# signal-generator.net
KiCad netlist of a schematic drawn in EAGLE
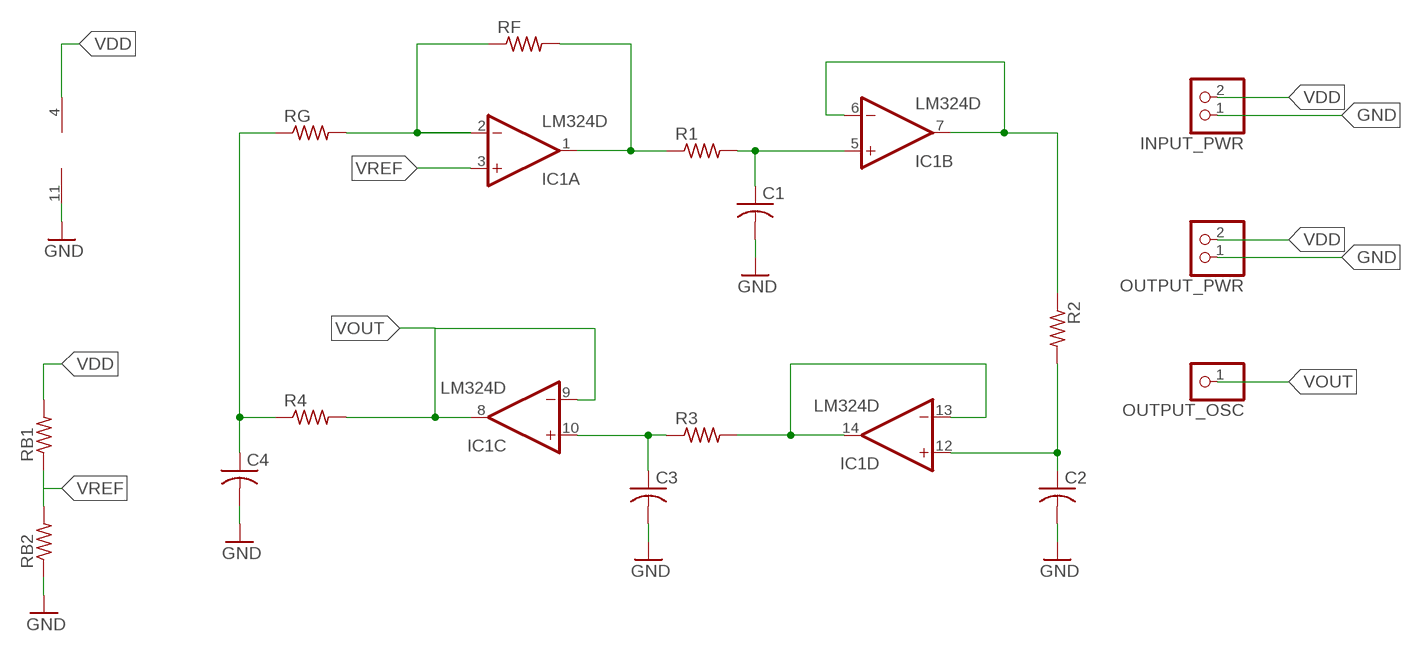
[diagram p0: schematic, sheet 1]

(export (version "E")
  (design (tool "Eeschema 10.0.6"))
  (components
    (comp (ref "C1")
      (value "C-USC0805")
      (footprint "eagle-import:C0805")
      (libsource (lib "eagle-import") (part "C-USC0805"))
    )
    (comp (ref "C2")
      (value "C-USC0805")
      (footprint "eagle-import:C0805")
      (libsource (lib "eagle-import") (part "C-USC0805"))
    )
    (comp (ref "C3")
      (value "C-USC0805")
      (footprint "eagle-import:C0805")
      (libsource (lib "eagle-import") (part "C-USC0805"))
    )
    (comp (ref "C4")
      (value "C-USC0805")
      (footprint "eagle-import:C0805")
      (libsource (lib "eagle-import") (part "C-USC0805"))
    )
    (comp (ref "IC1")
      (value "LM324D")
      (footprint "eagle-import:SO14")
      (libsource (lib "eagle-import") (part "LM324D"))
    )
    (comp (ref "INPUT_PWR")
      (value "PINHD-1X2/90")
      (footprint "eagle-import:1X02_90")
      (libsource (lib "eagle-import") (part "PINHD-1X2/90"))
    )
    (comp (ref "OUTPUT_OSC")
      (value "PINHD-1X1")
      (footprint "eagle-import:1X01")
      (libsource (lib "eagle-import") (part "PINHD-1X1"))
    )
    (comp (ref "OUTPUT_PWR")
      (value "PINHD-1X2/90")
      (footprint "eagle-import:1X02_90")
      (libsource (lib "eagle-import") (part "PINHD-1X2/90"))
    )
    (comp (ref "R1")
      (value "R-US_R0805")
      (footprint "eagle-import:R0805")
      (libsource (lib "eagle-import") (part "R-US_R0805"))
    )
    (comp (ref "R2")
      (value "R-US_R0805")
      (footprint "eagle-import:R0805")
      (libsource (lib "eagle-import") (part "R-US_R0805"))
    )
    (comp (ref "R3")
      (value "R-US_R0805")
      (footprint "eagle-import:R0805")
      (libsource (lib "eagle-import") (part "R-US_R0805"))
    )
    (comp (ref "R4")
      (value "R-US_R0805")
      (footprint "eagle-import:R0805")
      (libsource (lib "eagle-import") (part "R-US_R0805"))
    )
    (comp (ref "RB1")
      (value "R-US_R0805")
      (footprint "eagle-import:R0805")
      (libsource (lib "eagle-import") (part "R-US_R0805"))
    )
    (comp (ref "RB2")
      (value "R-US_R0805")
      (footprint "eagle-import:R0805")
      (libsource (lib "eagle-import") (part "R-US_R0805"))
    )
    (comp (ref "RF")
      (value "R-US_R0805")
      (footprint "eagle-import:R0805")
      (libsource (lib "eagle-import") (part "R-US_R0805"))
    )
    (comp (ref "RG")
      (value "R-US_R0805")
      (footprint "eagle-import:R0805")
      (libsource (lib "eagle-import") (part "R-US_R0805"))
    )
  )
  (nets
    (net (code "1") (name "GND") (class "Default")
      (node (ref "C1") (pin "2") (pinfunction "2_2") (pintype "passive"))
      (node (ref "C2") (pin "2") (pinfunction "2_2") (pintype "passive"))
      (node (ref "C3") (pin "2") (pinfunction "2_2") (pintype "passive"))
      (node (ref "C4") (pin "2") (pinfunction "2_2") (pintype "passive"))
      (node (ref "IC1") (pin "11") (pinfunction "V-_11") (pintype "power_in"))
      (node (ref "INPUT_PWR") (pin "1") (pinfunction "1_1") (pintype "passive"))
      (node (ref "OUTPUT_PWR") (pin "1") (pinfunction "1_1") (pintype "passive"))
      (node (ref "RB2") (pin "1") (pinfunction "1_1") (pintype "passive"))
    )
    (net (code "2") (name "Net-(C4-Pad1)") (class "Default")
      (node (ref "C4") (pin "1") (pinfunction "1_1") (pintype "passive"))
      (node (ref "R4") (pin "1") (pinfunction "1_1") (pintype "passive"))
      (node (ref "RG") (pin "1") (pinfunction "1_1") (pintype "passive"))
    )
    (net (code "3") (name "Net-(IC1A--IN)") (class "Default")
      (node (ref "IC1") (pin "2") (pinfunction "-IN_2") (pintype "input"))
      (node (ref "RF") (pin "1") (pinfunction "1_1") (pintype "passive"))
      (node (ref "RG") (pin "2") (pinfunction "2_2") (pintype "passive"))
    )
    (net (code "4") (name "Net-(IC1A-OUT)") (class "Default")
      (node (ref "IC1") (pin "1") (pinfunction "OUT_1") (pintype "output"))
      (node (ref "R1") (pin "1") (pinfunction "1_1") (pintype "passive"))
      (node (ref "RF") (pin "2") (pinfunction "2_2") (pintype "passive"))
    )
    (net (code "5") (name "Net-(IC1B-+IN)") (class "Default")
      (node (ref "C1") (pin "1") (pinfunction "1_1") (pintype "passive"))
      (node (ref "IC1") (pin "5") (pinfunction "+IN_5") (pintype "input"))
      (node (ref "R1") (pin "2") (pinfunction "2_2") (pintype "passive"))
    )
    (net (code "6") (name "Net-(IC1B--IN)") (class "Default")
      (node (ref "IC1") (pin "6") (pinfunction "-IN_6") (pintype "input"))
      (node (ref "IC1") (pin "7") (pinfunction "OUT_7") (pintype "output"))
      (node (ref "R2") (pin "1") (pinfunction "1_1") (pintype "passive"))
    )
    (net (code "7") (name "Net-(IC1C-+IN)") (class "Default")
      (node (ref "C3") (pin "1") (pinfunction "1_1") (pintype "passive"))
      (node (ref "IC1") (pin "10") (pinfunction "+IN_10") (pintype "input"))
      (node (ref "R3") (pin "1") (pinfunction "1_1") (pintype "passive"))
    )
    (net (code "8") (name "Net-(IC1D-+IN)") (class "Default")
      (node (ref "C2") (pin "1") (pinfunction "1_1") (pintype "passive"))
      (node (ref "IC1") (pin "12") (pinfunction "+IN_12") (pintype "input"))
      (node (ref "R2") (pin "2") (pinfunction "2_2") (pintype "passive"))
    )
    (net (code "9") (name "Net-(IC1D--IN)") (class "Default")
      (node (ref "IC1") (pin "13") (pinfunction "-IN_13") (pintype "input"))
      (node (ref "IC1") (pin "14") (pinfunction "OUT_14") (pintype "output"))
      (node (ref "R3") (pin "2") (pinfunction "2_2") (pintype "passive"))
    )
    (net (code "10") (name "VDD") (class "Default")
      (node (ref "IC1") (pin "4") (pinfunction "V+_4") (pintype "power_in"))
      (node (ref "INPUT_PWR") (pin "2") (pinfunction "2_2") (pintype "passive"))
      (node (ref "OUTPUT_PWR") (pin "2") (pinfunction "2_2") (pintype "passive"))
      (node (ref "RB1") (pin "2") (pinfunction "2_2") (pintype "passive"))
    )
    (net (code "11") (name "VOUT") (class "Default")
      (node (ref "IC1") (pin "8") (pinfunction "OUT_8") (pintype "output"))
      (node (ref "IC1") (pin "9") (pinfunction "-IN_9") (pintype "input"))
      (node (ref "OUTPUT_OSC") (pin "1") (pinfunction "1_1") (pintype "passive"))
      (node (ref "R4") (pin "2") (pinfunction "2_2") (pintype "passive"))
    )
    (net (code "12") (name "VREF") (class "Default")
      (node (ref "IC1") (pin "3") (pinfunction "+IN_3") (pintype "input"))
      (node (ref "RB1") (pin "1") (pinfunction "1_1") (pintype "passive"))
      (node (ref "RB2") (pin "2") (pinfunction "2_2") (pintype "passive"))
    )
  )
)
